# Proiect_TSC_v86.net
KiCad netlist of a schematic drawn in EAGLE
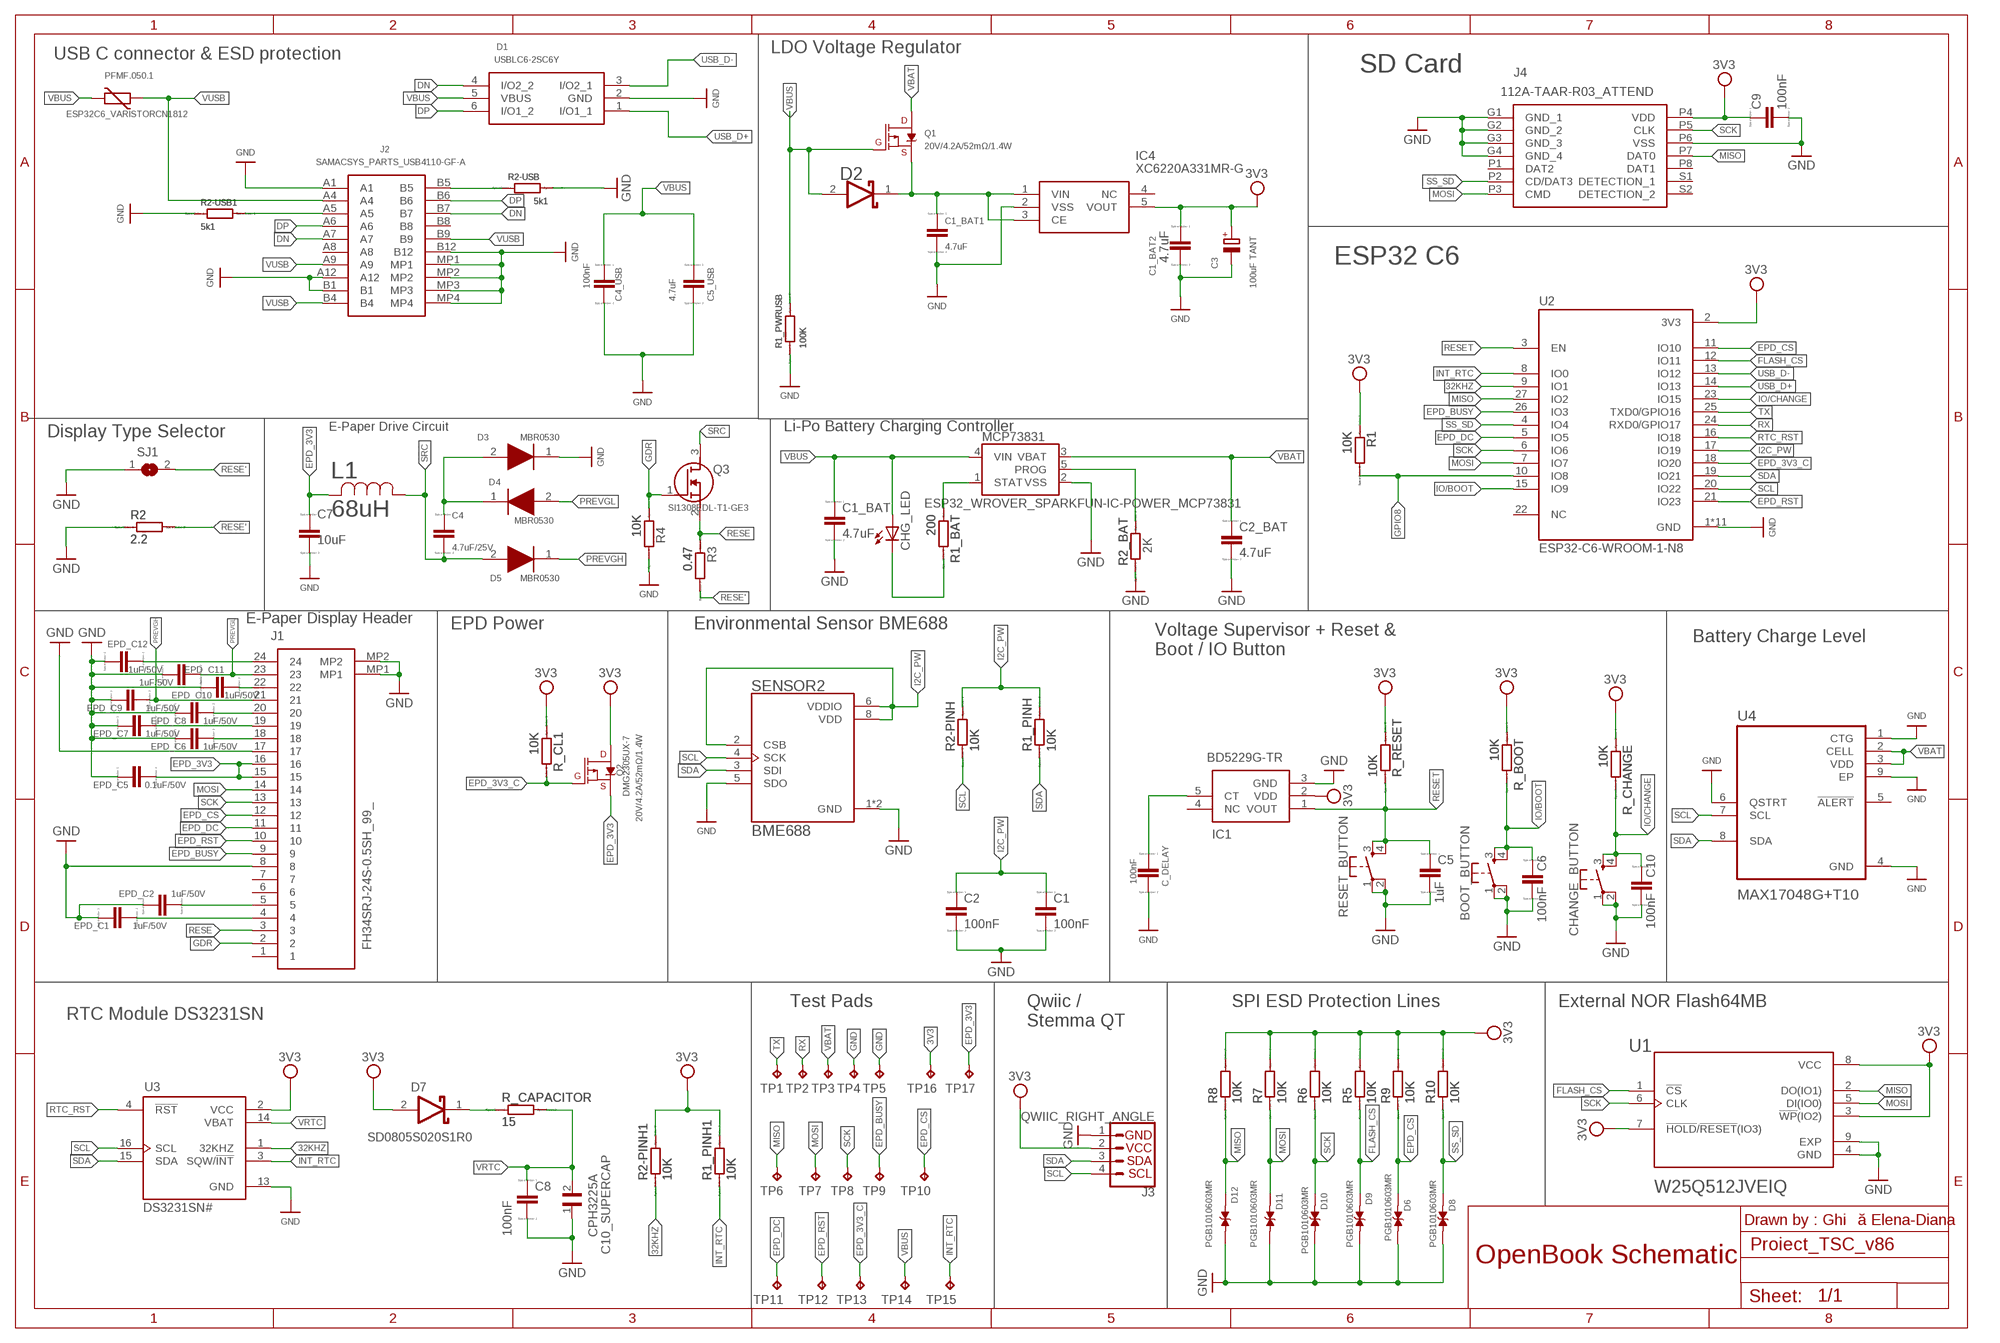
[diagram p0: schematic, sheet 1]

(export (version "E")
  (design (tool "Eeschema 10.0.6"))
  (components
    (comp (ref "BOOT_BUTTON")
      (value "BUTTON_CUSYOMV1")
      (footprint "eagle-import:MYBUTTON")
      (libsource (lib "eagle-import") (part "BUTTON_CUSYOMV1"))
    )
    (comp (ref "C1")
      (value "100nF")
      (footprint "eagle-import:ESP32_WROVER_EAGLE-LTSPICE_C0402")
      (libsource (lib "eagle-import") (part "ESP32_WROVER_EAGLE-LTSPICE_CC0402"))
    )
    (comp (ref "C1_BAT")
      (value "4.7uF")
      (footprint "eagle-import:ESP32_WROVER_EAGLE-LTSPICE_C0402")
      (libsource (lib "eagle-import") (part "ESP32_WROVER_EAGLE-LTSPICE_CC0402"))
    )
    (comp (ref "C1_BAT1")
      (value "4.7uF")
      (footprint "eagle-import:ESP32_WROVER_EAGLE-LTSPICE_C0402")
      (libsource (lib "eagle-import") (part "ESP32_WROVER_EAGLE-LTSPICE_CC0402"))
    )
    (comp (ref "C1_BAT2")
      (value "4.7uF")
      (footprint "eagle-import:ESP32_WROVER_EAGLE-LTSPICE_C0402")
      (libsource (lib "eagle-import") (part "ESP32_WROVER_EAGLE-LTSPICE_CC0402"))
    )
    (comp (ref "C2")
      (value "100nF")
      (footprint "eagle-import:ESP32_WROVER_EAGLE-LTSPICE_C0402")
      (libsource (lib "eagle-import") (part "ESP32_WROVER_EAGLE-LTSPICE_CC0402"))
    )
    (comp (ref "C2_BAT")
      (value "4.7uF")
      (footprint "eagle-import:ESP32_WROVER_EAGLE-LTSPICE_C0402")
      (libsource (lib "eagle-import") (part "ESP32_WROVER_EAGLE-LTSPICE_CC0402"))
    )
    (comp (ref "C3")
      (value "100uF TANT")
      (footprint "eagle-import:RCL_CT3528")
      (libsource (lib "eagle-import") (part "RCL_CPOL-EUCT3528"))
    )
    (comp (ref "C4")
      (value "4.7uF/25V")
      (footprint "eagle-import:ESP32_WROVER_EAGLE-LTSPICE_C0402")
      (libsource (lib "eagle-import") (part "ESP32_WROVER_EAGLE-LTSPICE_CC0402"))
    )
    (comp (ref "C4_USB")
      (value "100nF")
      (footprint "eagle-import:ESP32_WROVER_EAGLE-LTSPICE_C0402")
      (libsource (lib "eagle-import") (part "ESP32_WROVER_EAGLE-LTSPICE_CC0402"))
    )
    (comp (ref "C5")
      (value "1uF")
      (footprint "eagle-import:ESP32_WROVER_EAGLE-LTSPICE_C0402")
      (libsource (lib "eagle-import") (part "ESP32_WROVER_EAGLE-LTSPICE_CC0402"))
    )
    (comp (ref "C5_USB")
      (value "4.7uF")
      (footprint "eagle-import:ESP32_WROVER_EAGLE-LTSPICE_C0402")
      (libsource (lib "eagle-import") (part "ESP32_WROVER_EAGLE-LTSPICE_CC0402"))
    )
    (comp (ref "C6")
      (value "100nF")
      (footprint "eagle-import:ESP32_WROVER_EAGLE-LTSPICE_C0402")
      (libsource (lib "eagle-import") (part "ESP32_WROVER_EAGLE-LTSPICE_CC0402"))
    )
    (comp (ref "C7")
      (value "10uF")
      (footprint "eagle-import:ESP32_WROVER_EAGLE-LTSPICE_C0402")
      (libsource (lib "eagle-import") (part "ESP32_WROVER_EAGLE-LTSPICE_CC0402"))
    )
    (comp (ref "C8")
      (value "100nF")
      (footprint "eagle-import:ESP32_WROVER_EAGLE-LTSPICE_C0402")
      (libsource (lib "eagle-import") (part "ESP32_WROVER_EAGLE-LTSPICE_CC0402"))
    )
    (comp (ref "C9")
      (value "100nF")
      (footprint "eagle-import:ESP32_WROVER_EAGLE-LTSPICE_C0402")
      (libsource (lib "eagle-import") (part "ESP32_WROVER_EAGLE-LTSPICE_CC0402"))
    )
    (comp (ref "C10")
      (value "100nF")
      (footprint "eagle-import:ESP32_WROVER_EAGLE-LTSPICE_C0402")
      (libsource (lib "eagle-import") (part "ESP32_WROVER_EAGLE-LTSPICE_CC0402"))
    )
    (comp (ref "C10_SUPERCAP")
      (value "CPH3225A")
      (footprint "eagle-import:CAPCP3225X100N")
      (fields (field (name "MF") "Seiko Instruments"))
      (libsource (lib "eagle-import") (part "CPH3225A"))
    )
    (comp (ref "CHANGE_BUTTON")
      (value "BUTTON_CUSYOMV1")
      (footprint "eagle-import:MYBUTTON")
      (libsource (lib "eagle-import") (part "BUTTON_CUSYOMV1"))
    )
    (comp (ref "CHG_LED")
      (value "ADAFRUIT_LEDCHIP-LED0603")
      (footprint "eagle-import:ADAFRUIT_CHIP-LED0603")
      (libsource (lib "eagle-import") (part "ADAFRUIT_LEDCHIP-LED0603"))
    )
    (comp (ref "C_DELAY")
      (value "100nF")
      (footprint "eagle-import:ESP32_WROVER_EAGLE-LTSPICE_C0402")
      (libsource (lib "eagle-import") (part "ESP32_WROVER_EAGLE-LTSPICE_CC0402"))
    )
    (comp (ref "D1")
      (value "USBLC6-2SC6Y")
      (footprint "eagle-import:SOT95P280X145-6N")
      (fields (field (name "MF") "STMicroelectronics"))
      (libsource (lib "eagle-import") (part "USBLC6-2SC6Y"))
    )
    (comp (ref "D2")
      (value "ESP32_WROVER_AVX---SD0805S020S1R0_AVX_SD0805S020S1R0_0_0AVX_SD0805S020S1R0_0_0")
      (footprint "eagle-import:ESP32_WROVER_AVX---SD0805S020S1R0_AVX_SD0805S020S1R0_0")
      (fields
        (field (name "DIGIKEY_PART_NUMBER") "478-7800-1-ND")
        (field (name "MF") "AVX")
        (field (name "MOUSER_PART_NUMBER") "581-SD0805S020S1R0")
      )
      (libsource (lib "eagle-import") (part "ESP32_WROVER_AVX---SD0805S020S1R0_AVX_SD0805S020S1R0_0_0AVX_SD0805S020S1R0_0_0"))
    )
    (comp (ref "D3")
      (value "MBR0530")
      (footprint "eagle-import:SOD3716X135N")
      (fields (field (name "MF") "ON Semiconductor"))
      (libsource (lib "eagle-import") (part "MBR0530"))
    )
    (comp (ref "D4")
      (value "MBR0530")
      (footprint "eagle-import:SOD3716X135N")
      (fields (field (name "MF") "ON Semiconductor"))
      (libsource (lib "eagle-import") (part "MBR0530"))
    )
    (comp (ref "D5")
      (value "MBR0530")
      (footprint "eagle-import:SOD3716X135N")
      (fields (field (name "MF") "ON Semiconductor"))
      (libsource (lib "eagle-import") (part "MBR0530"))
    )
    (comp (ref "D6")
      (value "PGB1010603MR")
      (footprint "eagle-import:DIOC1608X36N")
      (fields (field (name "MF") "Littelfuse Inc."))
      (libsource (lib "eagle-import") (part "PGB1010603MR"))
    )
    (comp (ref "D7")
      (value "ESP32_WROVER_AVX---SD0805S020S1R0_AVX_SD0805S020S1R0_0_0AVX_SD0805S020S1R0_0_0")
      (footprint "eagle-import:ESP32_WROVER_AVX---SD0805S020S1R0_AVX_SD0805S020S1R0_0")
      (fields
        (field (name "DIGIKEY_PART_NUMBER") "478-7800-1-ND")
        (field (name "MF") "AVX")
        (field (name "MOUSER_PART_NUMBER") "581-SD0805S020S1R0")
      )
      (libsource (lib "eagle-import") (part "ESP32_WROVER_AVX---SD0805S020S1R0_AVX_SD0805S020S1R0_0_0AVX_SD0805S020S1R0_0_0"))
    )
    (comp (ref "D8")
      (value "PGB1010603MR")
      (footprint "eagle-import:DIOC1608X36N")
      (fields (field (name "MF") "Littelfuse Inc."))
      (libsource (lib "eagle-import") (part "PGB1010603MR"))
    )
    (comp (ref "D9")
      (value "PGB1010603MR")
      (footprint "eagle-import:DIOC1608X36N")
      (fields (field (name "MF") "Littelfuse Inc."))
      (libsource (lib "eagle-import") (part "PGB1010603MR"))
    )
    (comp (ref "D10")
      (value "PGB1010603MR")
      (footprint "eagle-import:DIOC1608X36N")
      (fields (field (name "MF") "Littelfuse Inc."))
      (libsource (lib "eagle-import") (part "PGB1010603MR"))
    )
    (comp (ref "D11")
      (value "PGB1010603MR")
      (footprint "eagle-import:DIOC1608X36N")
      (fields (field (name "MF") "Littelfuse Inc."))
      (libsource (lib "eagle-import") (part "PGB1010603MR"))
    )
    (comp (ref "D12")
      (value "PGB1010603MR")
      (footprint "eagle-import:DIOC1608X36N")
      (fields (field (name "MF") "Littelfuse Inc."))
      (libsource (lib "eagle-import") (part "PGB1010603MR"))
    )
    (comp (ref "EPD_C1")
      (value "1uF/50V")
      (footprint "eagle-import:ESP32_WROVER_EAGLE-LTSPICE_C0402")
      (libsource (lib "eagle-import") (part "ESP32_WROVER_EAGLE-LTSPICE_CC0402"))
    )
    (comp (ref "EPD_C2")
      (value "1uF/50V")
      (footprint "eagle-import:ESP32_WROVER_EAGLE-LTSPICE_C0402")
      (libsource (lib "eagle-import") (part "ESP32_WROVER_EAGLE-LTSPICE_CC0402"))
    )
    (comp (ref "EPD_C5")
      (value "0.1uF/50V")
      (footprint "eagle-import:ESP32_WROVER_EAGLE-LTSPICE_C0402")
      (libsource (lib "eagle-import") (part "ESP32_WROVER_EAGLE-LTSPICE_CC0402"))
    )
    (comp (ref "EPD_C6")
      (value "1uF/50V")
      (footprint "eagle-import:ESP32_WROVER_EAGLE-LTSPICE_C0402")
      (libsource (lib "eagle-import") (part "ESP32_WROVER_EAGLE-LTSPICE_CC0402"))
    )
    (comp (ref "EPD_C7")
      (value "1uF/50V")
      (footprint "eagle-import:ESP32_WROVER_EAGLE-LTSPICE_C0402")
      (libsource (lib "eagle-import") (part "ESP32_WROVER_EAGLE-LTSPICE_CC0402"))
    )
    (comp (ref "EPD_C8")
      (value "1uF/50V")
      (footprint "eagle-import:ESP32_WROVER_EAGLE-LTSPICE_C0402")
      (libsource (lib "eagle-import") (part "ESP32_WROVER_EAGLE-LTSPICE_CC0402"))
    )
    (comp (ref "EPD_C9")
      (value "1uF/50V")
      (footprint "eagle-import:ESP32_WROVER_EAGLE-LTSPICE_C0402")
      (libsource (lib "eagle-import") (part "ESP32_WROVER_EAGLE-LTSPICE_CC0402"))
    )
    (comp (ref "EPD_C10")
      (value "1uF/50V")
      (footprint "eagle-import:ESP32_WROVER_EAGLE-LTSPICE_C0402")
      (libsource (lib "eagle-import") (part "ESP32_WROVER_EAGLE-LTSPICE_CC0402"))
    )
    (comp (ref "EPD_C11")
      (value "1uF/50V")
      (footprint "eagle-import:ESP32_WROVER_EAGLE-LTSPICE_C0402")
      (libsource (lib "eagle-import") (part "ESP32_WROVER_EAGLE-LTSPICE_CC0402"))
    )
    (comp (ref "EPD_C12")
      (value "1uF/50V")
      (footprint "eagle-import:ESP32_WROVER_EAGLE-LTSPICE_C0402")
      (libsource (lib "eagle-import") (part "ESP32_WROVER_EAGLE-LTSPICE_CC0402"))
    )
    (comp (ref "IC1")
      (value "BD5229G-TR")
      (footprint "eagle-import:SOT95P280X125-5N")
      (fields (field (name "MOUSER_PART_NUMBER") "755-BD5229G-TR"))
      (libsource (lib "eagle-import") (part "BD5229G-TR"))
    )
    (comp (ref "IC4")
      (value "XC6220A331MR-G")
      (footprint "eagle-import:SOT95P280X120-5N")
      (fields (field (name "MOUSER_PART_NUMBER") "865-XC6220A331MR-G"))
      (libsource (lib "eagle-import") (part "XC6220A331MR-G"))
    )
    (comp (ref "J1")
      (value "FH34SRJ-24S-0.5SH_99_")
      (footprint "eagle-import:FH34SRJ24S05SH99")
      (fields
        (field (name "MANUFACTURER_PART_NUMBER") "FH34SRJ-24S-0.5SH(99)")
        (field (name "MOUSER_PART_NUMBER") "798-FH34SRJ24S05SH99")
      )
      (libsource (lib "eagle-import") (part "FH34SRJ-24S-0.5SH_99_"))
    )
    (comp (ref "J2")
      (value "SAMACSYS_PARTS_USB4110-GF-A")
      (footprint "eagle-import:SAMACSYS_PARTS_USB4110GFA")
      (fields
        (field (name "MANUFACTURER_PART_NUMBER") "USB4110-GF-A")
        (field (name "MOUSER_PART_NUMBER") "640-USB4110-GF-A")
      )
      (libsource (lib "eagle-import") (part "SAMACSYS_PARTS_USB4110-GF-A"))
    )
    (comp (ref "J3")
      (value "QWIIC_RIGHT_ANGLE")
      (footprint "eagle-import:JST04_1MM_RA")
      (libsource (lib "eagle-import") (part "QWIIC_CONNECTORJS-1MM"))
    )
    (comp (ref "J4")
      (value "112A-TAAR-R03_ATTEND")
      (footprint "eagle-import:112ATAARR03ATTEND")
      (fields (field (name "MANUFACTURER_PART_NUMBER") "112A-TAAR-R03 ATTEND"))
      (libsource (lib "eagle-import") (part "112A-TAAR-R03_ATTEND"))
    )
    (comp (ref "L1")
      (value "68uH")
      (footprint "eagle-import:IND_4828-WE-TPC_WRE")
      (fields
        (field (name "MANUFACTURER_PART_NUMBER") "744043680")
        (field (name "COPYRIGHT") "Copyright (C) 2024 Ultra Librarian. All rights reserved.")
      )
      (libsource (lib "eagle-import") (part "744043680IND_4828-WE-TPC_WRE"))
    )
    (comp (ref "MCP73831")
      (value "ESP32_WROVER_SPARKFUN-IC-POWER_MCP73831")
      (footprint "eagle-import:ESP32_WROVER_SPARKFUN-IC-POWER_SOT23-5")
      (libsource (lib "eagle-import") (part "ESP32_WROVER_SPARKFUN-IC-POWER_MCP73831"))
    )
    (comp (ref "PFMF.050.1")
      (value "ESP32C6_VARISTORCN1812")
      (footprint "eagle-import:ESP32C6_VARISTOR_CT_CN1812")
      (libsource (lib "eagle-import") (part "ESP32C6_VARISTORCN1812"))
    )
    (comp (ref "Q1")
      (value "20V/4.2A/52mΩ/1.4W")
      (footprint "eagle-import:ESP32_WROVER_SPARKFUN-DISCRETESEMI_SOT23-3")
      (libsource (lib "eagle-import") (part "ESP32_WROVER_SPARKFUN-DISCRETESEMI_MOSFET_PCH-DMG2305UX-7"))
    )
    (comp (ref "Q2")
      (value "20V/4.2A/52mΩ/1.4W")
      (footprint "eagle-import:ESP32_WROVER_SPARKFUN-DISCRETESEMI_SOT23-3")
      (fields (field (name "THERMALLOSS") "2305 UX"))
      (libsource (lib "eagle-import") (part "ESP32_WROVER_SPARKFUN-DISCRETESEMI_MOSFET_PCH-DMG2305UX-7"))
    )
    (comp (ref "Q3")
      (value "SI1308EDL-T1-GE3")
      (footprint "eagle-import:SOT65P210X110-3N")
      (fields (field (name "MF") "Vishay Siliconix"))
      (libsource (lib "eagle-import") (part "SI1308EDL-T1-GE3"))
    )
    (comp (ref "R1")
      (value "10K")
      (footprint "eagle-import:ESP32_WROVER_EAGLE-LTSPICE_R0402")
      (libsource (lib "eagle-import") (part "ESP32_WROVER_EAGLE-LTSPICE_RR0402"))
    )
    (comp (ref "R1_BAT")
      (value "200")
      (footprint "eagle-import:ESP32_WROVER_EAGLE-LTSPICE_R0402")
      (libsource (lib "eagle-import") (part "ESP32_WROVER_EAGLE-LTSPICE_RR0402"))
    )
    (comp (ref "R1_PINH")
      (value "10K")
      (footprint "eagle-import:ESP32_WROVER_EAGLE-LTSPICE_R0402")
      (libsource (lib "eagle-import") (part "ESP32_WROVER_EAGLE-LTSPICE_RR0402"))
    )
    (comp (ref "R1_PINH1")
      (value "10K")
      (footprint "eagle-import:ESP32_WROVER_EAGLE-LTSPICE_R0402")
      (libsource (lib "eagle-import") (part "ESP32_WROVER_EAGLE-LTSPICE_RR0402"))
    )
    (comp (ref "R1_PWRUSB")
      (value "100K")
      (footprint "eagle-import:ESP32_WROVER_EAGLE-LTSPICE_R0402")
      (libsource (lib "eagle-import") (part "ESP32_WROVER_EAGLE-LTSPICE_RR0402"))
    )
    (comp (ref "R2")
      (value "2.2")
      (footprint "eagle-import:ESP32_WROVER_EAGLE-LTSPICE_R0402")
      (libsource (lib "eagle-import") (part "ESP32_WROVER_EAGLE-LTSPICE_RR0402"))
    )
    (comp (ref "R2-PINH")
      (value "10K")
      (footprint "eagle-import:ESP32_WROVER_EAGLE-LTSPICE_R0402")
      (libsource (lib "eagle-import") (part "ESP32_WROVER_EAGLE-LTSPICE_RR0402"))
    )
    (comp (ref "R2-PINH1")
      (value "10K")
      (footprint "eagle-import:ESP32_WROVER_EAGLE-LTSPICE_R0402")
      (libsource (lib "eagle-import") (part "ESP32_WROVER_EAGLE-LTSPICE_RR0402"))
    )
    (comp (ref "R2-USB")
      (value "5k1")
      (footprint "eagle-import:ESP32_WROVER_EAGLE-LTSPICE_R0402")
      (libsource (lib "eagle-import") (part "ESP32_WROVER_EAGLE-LTSPICE_RR0402"))
    )
    (comp (ref "R2-USB1")
      (value "5k1")
      (footprint "eagle-import:ESP32_WROVER_EAGLE-LTSPICE_R0402")
      (libsource (lib "eagle-import") (part "ESP32_WROVER_EAGLE-LTSPICE_RR0402"))
    )
    (comp (ref "R2_BAT")
      (value "2K")
      (footprint "eagle-import:ESP32_WROVER_EAGLE-LTSPICE_R0402")
      (libsource (lib "eagle-import") (part "ESP32_WROVER_EAGLE-LTSPICE_RR0402"))
    )
    (comp (ref "R3")
      (value "0.47")
      (footprint "eagle-import:ESP32_WROVER_EAGLE-LTSPICE_R0402")
      (libsource (lib "eagle-import") (part "ESP32_WROVER_EAGLE-LTSPICE_RR0402"))
    )
    (comp (ref "R4")
      (value "10K")
      (footprint "eagle-import:ESP32_WROVER_EAGLE-LTSPICE_R0402")
      (libsource (lib "eagle-import") (part "ESP32_WROVER_EAGLE-LTSPICE_RR0402"))
    )
    (comp (ref "R5")
      (value "10K")
      (footprint "eagle-import:ESP32_WROVER_EAGLE-LTSPICE_R0402")
      (libsource (lib "eagle-import") (part "ESP32_WROVER_EAGLE-LTSPICE_RR0402"))
    )
    (comp (ref "R6")
      (value "10K")
      (footprint "eagle-import:ESP32_WROVER_EAGLE-LTSPICE_R0402")
      (libsource (lib "eagle-import") (part "ESP32_WROVER_EAGLE-LTSPICE_RR0402"))
    )
    (comp (ref "R7")
      (value "10K")
      (footprint "eagle-import:ESP32_WROVER_EAGLE-LTSPICE_R0402")
      (libsource (lib "eagle-import") (part "ESP32_WROVER_EAGLE-LTSPICE_RR0402"))
    )
    (comp (ref "R8")
      (value "10K")
      (footprint "eagle-import:ESP32_WROVER_EAGLE-LTSPICE_R0402")
      (libsource (lib "eagle-import") (part "ESP32_WROVER_EAGLE-LTSPICE_RR0402"))
    )
    (comp (ref "R9")
      (value "10K")
      (footprint "eagle-import:ESP32_WROVER_EAGLE-LTSPICE_R0402")
      (libsource (lib "eagle-import") (part "ESP32_WROVER_EAGLE-LTSPICE_RR0402"))
    )
    (comp (ref "R10")
      (value "10K")
      (footprint "eagle-import:ESP32_WROVER_EAGLE-LTSPICE_R0402")
      (libsource (lib "eagle-import") (part "ESP32_WROVER_EAGLE-LTSPICE_RR0402"))
    )
    (comp (ref "RESET_BUTTON")
      (value "BUTTON_CUSYOMV1")
      (footprint "eagle-import:MYBUTTON")
      (libsource (lib "eagle-import") (part "BUTTON_CUSYOMV1"))
    )
    (comp (ref "R_BOOT")
      (value "10K")
      (footprint "eagle-import:ESP32_WROVER_EAGLE-LTSPICE_R0402")
      (libsource (lib "eagle-import") (part "ESP32_WROVER_EAGLE-LTSPICE_RR0402"))
    )
    (comp (ref "R_CAPACITOR")
      (value "15")
      (footprint "eagle-import:ESP32_WROVER_EAGLE-LTSPICE_R0402")
      (libsource (lib "eagle-import") (part "ESP32_WROVER_EAGLE-LTSPICE_RR0402"))
    )
    (comp (ref "R_CHANGE")
      (value "10K")
      (footprint "eagle-import:ESP32_WROVER_EAGLE-LTSPICE_R0402")
      (libsource (lib "eagle-import") (part "ESP32_WROVER_EAGLE-LTSPICE_RR0402"))
    )
    (comp (ref "R_CL1")
      (value "10K")
      (footprint "eagle-import:ESP32_WROVER_EAGLE-LTSPICE_R0402")
      (libsource (lib "eagle-import") (part "ESP32_WROVER_EAGLE-LTSPICE_RR0402"))
    )
    (comp (ref "R_RESET")
      (value "10K")
      (footprint "eagle-import:ESP32_WROVER_EAGLE-LTSPICE_R0402")
      (libsource (lib "eagle-import") (part "ESP32_WROVER_EAGLE-LTSPICE_RR0402"))
    )
    (comp (ref "SENSOR2")
      (value "BME688")
      (footprint "eagle-import:ESP32_WROVER_BME680_PSON80P300X300X100-8N")
      (fields (field (name "MF") "Bosch Sensortec") (field (name "MP") "BME680"))
      (libsource (lib "eagle-import") (part "ESP32_WROVER_BME680_BME680"))
    )
    (comp (ref "SJ1") (value "SJ") (footprint "eagle-import:SJ") (libsource (lib "eagle-import") (part "SJ")))
    (comp (ref "TP1")
      (value "TPTP20R")
      (footprint "eagle-import:TP20R")
      (libsource (lib "eagle-import") (part "TPTP20R"))
    )
    (comp (ref "TP2")
      (value "TPTP20R")
      (footprint "eagle-import:TP20R")
      (libsource (lib "eagle-import") (part "TPTP20R"))
    )
    (comp (ref "TP3")
      (value "TPTP20R")
      (footprint "eagle-import:TP20R")
      (libsource (lib "eagle-import") (part "TPTP20R"))
    )
    (comp (ref "TP4")
      (value "TPTP20R")
      (footprint "eagle-import:TP20R")
      (libsource (lib "eagle-import") (part "TPTP20R"))
    )
    (comp (ref "TP5")
      (value "TPTP20R")
      (footprint "eagle-import:TP20R")
      (libsource (lib "eagle-import") (part "TPTP20R"))
    )
    (comp (ref "TP6")
      (value "TPTP20R")
      (footprint "eagle-import:TP20R")
      (libsource (lib "eagle-import") (part "TPTP20R"))
    )
    (comp (ref "TP7")
      (value "TPTP20R")
      (footprint "eagle-import:TP20R")
      (libsource (lib "eagle-import") (part "TPTP20R"))
    )
    (comp (ref "TP8")
      (value "TPTP20R")
      (footprint "eagle-import:TP20R")
      (libsource (lib "eagle-import") (part "TPTP20R"))
    )
    (comp (ref "TP9")
      (value "TPTP20R")
      (footprint "eagle-import:TP20R")
      (libsource (lib "eagle-import") (part "TPTP20R"))
    )
    (comp (ref "TP10")
      (value "TPTP20R")
      (footprint "eagle-import:TP20R")
      (libsource (lib "eagle-import") (part "TPTP20R"))
    )
    (comp (ref "TP11")
      (value "TPTP20R")
      (footprint "eagle-import:TP20R")
      (libsource (lib "eagle-import") (part "TPTP20R"))
    )
    (comp (ref "TP12")
      (value "TPTP20R")
      (footprint "eagle-import:TP20R")
      (libsource (lib "eagle-import") (part "TPTP20R"))
    )
    (comp (ref "TP13")
      (value "TPTP20R")
      (footprint "eagle-import:TP20R")
      (libsource (lib "eagle-import") (part "TPTP20R"))
    )
    (comp (ref "TP14")
      (value "TPTP20R")
      (footprint "eagle-import:TP20R")
      (libsource (lib "eagle-import") (part "TPTP20R"))
    )
    (comp (ref "TP15")
      (value "TPTP20R")
      (footprint "eagle-import:TP20R")
      (libsource (lib "eagle-import") (part "TPTP20R"))
    )
    (comp (ref "TP16")
      (value "TPTP20R")
      (footprint "eagle-import:TP20R")
      (libsource (lib "eagle-import") (part "TPTP20R"))
    )
    (comp (ref "TP17")
      (value "TPTP20R")
      (footprint "eagle-import:TP20R")
      (libsource (lib "eagle-import") (part "TPTP20R"))
    )
    (comp (ref "U1")
      (value "W25Q512JVEIQ")
      (footprint "eagle-import:SON127P600X800X80-9N")
      (fields (field (name "MF") "Winbond Electronics"))
      (libsource (lib "eagle-import") (part "W25Q512JVEIQ"))
    )
    (comp (ref "U2")
      (value "ESP32-C6-WROOM-1-N8")
      (footprint "eagle-import:XCVR_ESP32-C6-WROOM-1-N8")
      (fields (field (name "MF") "Espressif Systems"))
      (libsource (lib "eagle-import") (part "ESP32-C6-WROOM-1-N8"))
    )
    (comp (ref "U3")
      (value "DS3231SN#")
      (footprint "eagle-import:SOIC127P1032X265-16N")
      (fields (field (name "MF") "Analog Devices"))
      (libsource (lib "eagle-import") (part "DS3231SN#"))
    )
    (comp (ref "U4")
      (value "MAX17048G+T10")
      (footprint "eagle-import:SON50P200X200X80-9N")
      (fields (field (name "MF") "Analog Devices"))
      (libsource (lib "eagle-import") (part "MAX17048G+T10"))
    )
  )
  (nets
    (net (code "1") (name "3V3") (class "Default")
      (node (ref "C1_BAT2") (pin "1") (pinfunction "1_1") (pintype "passive"))
      (node (ref "C3") (pin "+") (pinfunction "+_+") (pintype "passive"))
      (node (ref "C9") (pin "1") (pinfunction "1_1") (pintype "passive"))
      (node (ref "D7") (pin "2") (pinfunction "ANODE_2") (pintype "bidirectional"))
      (node (ref "IC1") (pin "2") (pinfunction "VDD_2") (pintype "bidirectional"))
      (node (ref "IC4") (pin "5") (pinfunction "VOUT_5") (pintype "bidirectional"))
      (node (ref "J3") (pin "2") (pinfunction "2_2") (pintype "power_in"))
      (node (ref "J4") (pin "P4") (pinfunction "VDD_P4") (pintype "bidirectional"))
      (node (ref "Q2") (pin "3") (pinfunction "D_3") (pintype "bidirectional"))
      (node (ref "R1") (pin "1") (pinfunction "1_1") (pintype "passive"))
      (node (ref "R10") (pin "2") (pinfunction "2_2") (pintype "passive"))
      (node (ref "R1_PINH1") (pin "2") (pinfunction "2_2") (pintype "passive"))
      (node (ref "R2-PINH1") (pin "2") (pinfunction "2_2") (pintype "passive"))
      (node (ref "R5") (pin "2") (pinfunction "2_2") (pintype "passive"))
      (node (ref "R6") (pin "2") (pinfunction "2_2") (pintype "passive"))
      (node (ref "R7") (pin "2") (pinfunction "2_2") (pintype "passive"))
      (node (ref "R8") (pin "2") (pinfunction "2_2") (pintype "passive"))
      (node (ref "R9") (pin "2") (pinfunction "2_2") (pintype "passive"))
      (node (ref "R_BOOT") (pin "1") (pinfunction "1_1") (pintype "passive"))
      (node (ref "R_CHANGE") (pin "1") (pinfunction "1_1") (pintype "passive"))
      (node (ref "R_CL1") (pin "1") (pinfunction "1_1") (pintype "passive"))
      (node (ref "R_RESET") (pin "2") (pinfunction "2_2") (pintype "passive"))
      (node (ref "TP16") (pin "TP") (pinfunction "TP_TP") (pintype "input"))
      (node (ref "U1") (pin "3") (pinfunction "~{WP}(IO2)_3") (pintype "bidirectional"))
      (node (ref "U1") (pin "7") (pinfunction "~{HOLD}/~{RESET}(IO3)_7") (pintype "bidirectional"))
      (node (ref "U1") (pin "8") (pinfunction "VCC_8") (pintype "power_in"))
      (node (ref "U2") (pin "2") (pinfunction "3V3_2") (pintype "power_in"))
      (node (ref "U3") (pin "2") (pinfunction "VCC_2") (pintype "power_in"))
    )
    (net (code "2") (name "32KHZ") (class "Default")
      (node (ref "R2-PINH1") (pin "1") (pinfunction "1_1") (pintype "passive"))
      (node (ref "U2") (pin "9") (pinfunction "IO1_9") (pintype "bidirectional"))
      (node (ref "U3") (pin "1") (pinfunction "32KHZ_1") (pintype "output"))
    )
    (net (code "3") (name "DN") (class "Default")
      (node (ref "D1") (pin "4") (pinfunction "I/O2_2_4") (pintype "bidirectional"))
      (node (ref "J2") (pin "A7") (pinfunction "A7_A7") (pintype "bidirectional"))
      (node (ref "J2") (pin "B7") (pinfunction "B7_B7") (pintype "bidirectional"))
    )
    (net (code "4") (name "DP") (class "Default")
      (node (ref "D1") (pin "6") (pinfunction "I/O1_2_6") (pintype "bidirectional"))
      (node (ref "J2") (pin "A6") (pinfunction "A6_A6") (pintype "bidirectional"))
      (node (ref "J2") (pin "B6") (pinfunction "B6_B6") (pintype "bidirectional"))
    )
    (net (code "5") (name "EPD_3V3") (class "Default")
      (node (ref "C7") (pin "1") (pinfunction "1_1") (pintype "passive"))
      (node (ref "EPD_C5") (pin "2") (pinfunction "2_2") (pintype "passive"))
      (node (ref "J1") (pin "15") (pinfunction "15_15") (pintype "bidirectional"))
      (node (ref "J1") (pin "16") (pinfunction "16_16") (pintype "bidirectional"))
      (node (ref "L1") (pin "2") (pinfunction "2_2") (pintype "passive"))
      (node (ref "Q2") (pin "2") (pinfunction "S_2") (pintype "bidirectional"))
      (node (ref "TP17") (pin "TP") (pinfunction "TP_TP") (pintype "input"))
    )
    (net (code "6") (name "EPD_3V3_C") (class "Default")
      (node (ref "Q2") (pin "1") (pinfunction "G_1") (pintype "bidirectional"))
      (node (ref "R_CL1") (pin "2") (pinfunction "2_2") (pintype "passive"))
      (node (ref "TP13") (pin "TP") (pinfunction "TP_TP") (pintype "input"))
      (node (ref "U2") (pin "18") (pinfunction "IO20_18") (pintype "bidirectional"))
    )
    (net (code "7") (name "EPD_BUSY") (class "Default")
      (node (ref "J1") (pin "9") (pinfunction "9_9") (pintype "bidirectional"))
      (node (ref "TP9") (pin "TP") (pinfunction "TP_TP") (pintype "input"))
      (node (ref "U2") (pin "26") (pinfunction "IO3_26") (pintype "bidirectional"))
    )
    (net (code "8") (name "EPD_CS") (class "Default")
      (node (ref "D6") (pin "1") (pinfunction "1_1") (pintype "passive"))
      (node (ref "J1") (pin "12") (pinfunction "12_12") (pintype "bidirectional"))
      (node (ref "R9") (pin "1") (pinfunction "1_1") (pintype "passive"))
      (node (ref "TP10") (pin "TP") (pinfunction "TP_TP") (pintype "input"))
      (node (ref "U2") (pin "11") (pinfunction "IO10_11") (pintype "bidirectional"))
    )
    (net (code "9") (name "EPD_DC") (class "Default")
      (node (ref "J1") (pin "11") (pinfunction "11_11") (pintype "bidirectional"))
      (node (ref "TP11") (pin "TP") (pinfunction "TP_TP") (pintype "input"))
      (node (ref "U2") (pin "5") (pinfunction "IO5_5") (pintype "bidirectional"))
    )
    (net (code "10") (name "EPD_RST") (class "Default")
      (node (ref "J1") (pin "10") (pinfunction "10_10") (pintype "bidirectional"))
      (node (ref "TP12") (pin "TP") (pinfunction "TP_TP") (pintype "input"))
      (node (ref "U2") (pin "21") (pinfunction "IO23_21") (pintype "bidirectional"))
    )
    (net (code "11") (name "FLASH_CS") (class "Default")
      (node (ref "D9") (pin "1") (pinfunction "1_1") (pintype "passive"))
      (node (ref "R5") (pin "1") (pinfunction "1_1") (pintype "passive"))
      (node (ref "U1") (pin "1") (pinfunction "~{CS}_1") (pintype "input"))
      (node (ref "U2") (pin "12") (pinfunction "IO11_12") (pintype "bidirectional"))
    )
    (net (code "12") (name "GDR") (class "Default")
      (node (ref "J1") (pin "2") (pinfunction "2_2") (pintype "bidirectional"))
      (node (ref "Q3") (pin "1") (pinfunction "G_1") (pintype "bidirectional"))
      (node (ref "R4") (pin "1") (pinfunction "1_1") (pintype "passive"))
    )
    (net (code "13") (name "GND") (class "Default")
      (node (ref "BOOT_BUTTON") (pin "1") (pinfunction "1_1") (pintype "passive"))
      (node (ref "BOOT_BUTTON") (pin "2") (pinfunction "2_2") (pintype "passive"))
      (node (ref "C1") (pin "2") (pinfunction "2_2") (pintype "passive"))
      (node (ref "C10") (pin "2") (pinfunction "2_2") (pintype "passive"))
      (node (ref "C10_SUPERCAP") (pin "1") (pinfunction "1_1") (pintype "passive"))
      (node (ref "C1_BAT") (pin "2") (pinfunction "2_2") (pintype "passive"))
      (node (ref "C1_BAT1") (pin "2") (pinfunction "2_2") (pintype "passive"))
      (node (ref "C1_BAT2") (pin "2") (pinfunction "2_2") (pintype "passive"))
      (node (ref "C2") (pin "2") (pinfunction "2_2") (pintype "passive"))
      (node (ref "C2_BAT") (pin "2") (pinfunction "2_2") (pintype "passive"))
      (node (ref "C3") (pin "-") (pinfunction "-_-") (pintype "passive"))
      (node (ref "C4_USB") (pin "2") (pinfunction "2_2") (pintype "passive"))
      (node (ref "C5") (pin "2") (pinfunction "2_2") (pintype "passive"))
      (node (ref "C5_USB") (pin "2") (pinfunction "2_2") (pintype "passive"))
      (node (ref "C6") (pin "2") (pinfunction "2_2") (pintype "passive"))
      (node (ref "C7") (pin "2") (pinfunction "2_2") (pintype "passive"))
      (node (ref "C8") (pin "2") (pinfunction "2_2") (pintype "passive"))
      (node (ref "C9") (pin "2") (pinfunction "2_2") (pintype "passive"))
      (node (ref "CHANGE_BUTTON") (pin "1") (pinfunction "1_1") (pintype "passive"))
      (node (ref "CHANGE_BUTTON") (pin "2") (pinfunction "2_2") (pintype "passive"))
      (node (ref "C_DELAY") (pin "2") (pinfunction "2_2") (pintype "passive"))
      (node (ref "D1") (pin "2") (pinfunction "GND_2") (pintype "bidirectional"))
      (node (ref "D10") (pin "2") (pinfunction "2_2") (pintype "passive"))
      (node (ref "D11") (pin "2") (pinfunction "2_2") (pintype "passive"))
      (node (ref "D12") (pin "2") (pinfunction "2_2") (pintype "passive"))
      (node (ref "D3") (pin "1") (pinfunction "K_1") (pintype "bidirectional"))
      (node (ref "D6") (pin "2") (pinfunction "2_2") (pintype "passive"))
      (node (ref "D8") (pin "2") (pinfunction "2_2") (pintype "passive"))
      (node (ref "D9") (pin "2") (pinfunction "2_2") (pintype "passive"))
      (node (ref "EPD_C1") (pin "1") (pinfunction "1_1") (pintype "passive"))
      (node (ref "EPD_C10") (pin "1") (pinfunction "1_1") (pintype "passive"))
      (node (ref "EPD_C11") (pin "1") (pinfunction "1_1") (pintype "passive"))
      (node (ref "EPD_C12") (pin "1") (pinfunction "1_1") (pintype "passive"))
      (node (ref "EPD_C2") (pin "1") (pinfunction "1_1") (pintype "passive"))
      (node (ref "EPD_C5") (pin "1") (pinfunction "1_1") (pintype "passive"))
      (node (ref "EPD_C6") (pin "1") (pinfunction "1_1") (pintype "passive"))
      (node (ref "EPD_C7") (pin "1") (pinfunction "1_1") (pintype "passive"))
      (node (ref "EPD_C8") (pin "1") (pinfunction "1_1") (pintype "passive"))
      (node (ref "EPD_C9") (pin "1") (pinfunction "1_1") (pintype "passive"))
      (node (ref "IC1") (pin "3") (pinfunction "GND_3") (pintype "bidirectional"))
      (node (ref "IC4") (pin "2") (pinfunction "VSS_2") (pintype "bidirectional"))
      (node (ref "J1") (pin "17") (pinfunction "17_17") (pintype "bidirectional"))
      (node (ref "J1") (pin "8") (pinfunction "8_8") (pintype "bidirectional"))
      (node (ref "J1") (pin "MP1") (pinfunction "MP1_MP1") (pintype "bidirectional"))
      (node (ref "J1") (pin "MP2") (pinfunction "MP2_MP2") (pintype "bidirectional"))
      (node (ref "J2") (pin "A1") (pinfunction "A1_A1") (pintype "bidirectional"))
      (node (ref "J2") (pin "A12") (pinfunction "A12_A12") (pintype "bidirectional"))
      (node (ref "J2") (pin "B1") (pinfunction "B1_B1") (pintype "bidirectional"))
      (node (ref "J2") (pin "B12") (pinfunction "B12_B12") (pintype "bidirectional"))
      (node (ref "J2") (pin "MP1") (pinfunction "MP1_MP1") (pintype "bidirectional"))
      (node (ref "J2") (pin "MP2") (pinfunction "MP2_MP2") (pintype "bidirectional"))
      (node (ref "J2") (pin "MP3") (pinfunction "MP3_MP3") (pintype "bidirectional"))
      (node (ref "J2") (pin "MP4") (pinfunction "MP4_MP4") (pintype "bidirectional"))
      (node (ref "J3") (pin "1") (pinfunction "1_1") (pintype "power_in"))
      (node (ref "J4") (pin "G1") (pinfunction "GND_1_G1") (pintype "bidirectional"))
      (node (ref "J4") (pin "G2") (pinfunction "GND_2_G2") (pintype "bidirectional"))
      (node (ref "J4") (pin "G3") (pinfunction "GND_3_G3") (pintype "bidirectional"))
      (node (ref "J4") (pin "G4") (pinfunction "GND_4_G4") (pintype "bidirectional"))
      (node (ref "J4") (pin "P6") (pinfunction "VSS_P6") (pintype "bidirectional"))
      (node (ref "MCP73831") (pin "2") (pinfunction "VSS_2") (pintype "power_in"))
      (node (ref "R1_PWRUSB") (pin "1") (pinfunction "1_1") (pintype "passive"))
      (node (ref "R2") (pin "1") (pinfunction "1_1") (pintype "passive"))
      (node (ref "R2-USB") (pin "2") (pinfunction "2_2") (pintype "passive"))
      (node (ref "R2-USB1") (pin "1") (pinfunction "1_1") (pintype "passive"))
      (node (ref "R2_BAT") (pin "1") (pinfunction "1_1") (pintype "passive"))
      (node (ref "R4") (pin "2") (pinfunction "2_2") (pintype "passive"))
      (node (ref "RESET_BUTTON") (pin "1") (pinfunction "1_1") (pintype "passive"))
      (node (ref "RESET_BUTTON") (pin "2") (pinfunction "2_2") (pintype "passive"))
      (node (ref "SENSOR2") (pin "1") (pinfunction "GND_1") (pintype "power_in"))
      (node (ref "SENSOR2") (pin "5") (pinfunction "SDO_5") (pintype "bidirectional"))
      (node (ref "SENSOR2") (pin "7") (pinfunction "GND_7") (pintype "power_in"))
      (node (ref "SJ1") (pin "1") (pinfunction "1_1") (pintype "passive"))
      (node (ref "TP4") (pin "TP") (pinfunction "TP_TP") (pintype "input"))
      (node (ref "TP5") (pin "TP") (pinfunction "TP_TP") (pintype "input"))
      (node (ref "U1") (pin "4") (pinfunction "GND_4") (pintype "power_in"))
      (node (ref "U1") (pin "9") (pinfunction "EXP_9") (pintype "passive"))
      (node (ref "U2") (pin "1") (pinfunction "GND_1") (pintype "power_in"))
      (node (ref "U2") (pin "28") (pinfunction "GND_28") (pintype "power_in"))
      (node (ref "U2") (pin "29_1") (pinfunction "GND_29_1") (pintype "power_in"))
      (node (ref "U2") (pin "29_2") (pinfunction "GND_29_2") (pintype "power_in"))
      (node (ref "U2") (pin "29_3") (pinfunction "GND_29_3") (pintype "power_in"))
      (node (ref "U2") (pin "29_4") (pinfunction "GND_29_4") (pintype "power_in"))
      (node (ref "U2") (pin "29_5") (pinfunction "GND_29_5") (pintype "power_in"))
      (node (ref "U2") (pin "29_6") (pinfunction "GND_29_6") (pintype "power_in"))
      (node (ref "U2") (pin "29_7") (pinfunction "GND_29_7") (pintype "power_in"))
      (node (ref "U2") (pin "29_8") (pinfunction "GND_29_8") (pintype "power_in"))
      (node (ref "U2") (pin "29_9") (pinfunction "GND_29_9") (pintype "power_in"))
      (node (ref "U3") (pin "13") (pinfunction "GND_13") (pintype "power_in"))
      (node (ref "U4") (pin "1") (pinfunction "CTG_1") (pintype "power_in"))
      (node (ref "U4") (pin "4") (pinfunction "GND_4") (pintype "power_in"))
      (node (ref "U4") (pin "6") (pinfunction "QSTRT_6") (pintype "input"))
      (node (ref "U4") (pin "9") (pinfunction "EP_9") (pintype "power_in"))
    )
    (net (code "14") (name "GPIO8") (class "Default")
      (node (ref "R1") (pin "2") (pinfunction "2_2") (pintype "passive"))
      (node (ref "U2") (pin "10") (pinfunction "IO8_10") (pintype "bidirectional"))
    )
    (net (code "15") (name "I2C_PW") (class "Default")
      (node (ref "C1") (pin "1") (pinfunction "1_1") (pintype "passive"))
      (node (ref "C2") (pin "1") (pinfunction "1_1") (pintype "passive"))
      (node (ref "R1_PINH") (pin "2") (pinfunction "2_2") (pintype "passive"))
      (node (ref "R2-PINH") (pin "2") (pinfunction "2_2") (pintype "passive"))
      (node (ref "SENSOR2") (pin "2") (pinfunction "CSB_2") (pintype "input"))
      (node (ref "SENSOR2") (pin "6") (pinfunction "VDDIO_6") (pintype "power_in"))
      (node (ref "SENSOR2") (pin "8") (pinfunction "VDD_8") (pintype "power_in"))
      (node (ref "U2") (pin "17") (pinfunction "IO19_17") (pintype "bidirectional"))
    )
    (net (code "16") (name "INT_RTC") (class "Default")
      (node (ref "R1_PINH1") (pin "1") (pinfunction "1_1") (pintype "passive"))
      (node (ref "TP15") (pin "TP") (pinfunction "TP_TP") (pintype "input"))
      (node (ref "U2") (pin "8") (pinfunction "IO0_8") (pintype "bidirectional"))
      (node (ref "U3") (pin "3") (pinfunction "SQW/~{INT}_3") (pintype "output"))
    )
    (net (code "17") (name "IO{slash}BOOT") (class "Default")
      (node (ref "BOOT_BUTTON") (pin "3") (pinfunction "3_3") (pintype "passive"))
      (node (ref "BOOT_BUTTON") (pin "4") (pinfunction "4_4") (pintype "passive"))
      (node (ref "C6") (pin "1") (pinfunction "1_1") (pintype "passive"))
      (node (ref "R_BOOT") (pin "2") (pinfunction "2_2") (pintype "passive"))
      (node (ref "U2") (pin "15") (pinfunction "IO9_15") (pintype "bidirectional"))
    )
    (net (code "18") (name "IO{slash}CHANGE") (class "Default")
      (node (ref "C10") (pin "1") (pinfunction "1_1") (pintype "passive"))
      (node (ref "CHANGE_BUTTON") (pin "3") (pinfunction "3_3") (pintype "passive"))
      (node (ref "CHANGE_BUTTON") (pin "4") (pinfunction "4_4") (pintype "passive"))
      (node (ref "R_CHANGE") (pin "2") (pinfunction "2_2") (pintype "passive"))
      (node (ref "U2") (pin "23") (pinfunction "IO15_23") (pintype "bidirectional"))
    )
    (net (code "19") (name "MISO") (class "Default")
      (node (ref "D12") (pin "1") (pinfunction "1_1") (pintype "passive"))
      (node (ref "J4") (pin "P7") (pinfunction "DAT0_P7") (pintype "bidirectional"))
      (node (ref "R8") (pin "1") (pinfunction "1_1") (pintype "passive"))
      (node (ref "TP6") (pin "TP") (pinfunction "TP_TP") (pintype "input"))
      (node (ref "U1") (pin "2") (pinfunction "DO(IO1)_2") (pintype "bidirectional"))
      (node (ref "U2") (pin "27") (pinfunction "IO2_27") (pintype "bidirectional"))
    )
    (net (code "20") (name "MOSI") (class "Default")
      (node (ref "D11") (pin "1") (pinfunction "1_1") (pintype "passive"))
      (node (ref "J1") (pin "14") (pinfunction "14_14") (pintype "bidirectional"))
      (node (ref "J4") (pin "P3") (pinfunction "CMD_P3") (pintype "bidirectional"))
      (node (ref "R7") (pin "1") (pinfunction "1_1") (pintype "passive"))
      (node (ref "TP7") (pin "TP") (pinfunction "TP_TP") (pintype "input"))
      (node (ref "U1") (pin "5") (pinfunction "DI(IO0)_5") (pintype "bidirectional"))
      (node (ref "U2") (pin "7") (pinfunction "IO7_7") (pintype "bidirectional"))
    )
    (net (code "21") (name "Net-(CHG_LED-PadC)") (class "Default")
      (node (ref "CHG_LED") (pin "C") (pinfunction "C_C") (pintype "passive"))
      (node (ref "R1_BAT") (pin "2") (pinfunction "2_2") (pintype "passive"))
    )
    (net (code "22") (name "Net-(D2-CATHODE)") (class "Default")
      (node (ref "C1_BAT1") (pin "1") (pinfunction "1_1") (pintype "passive"))
      (node (ref "D2") (pin "1") (pinfunction "CATHODE_1") (pintype "bidirectional"))
      (node (ref "IC4") (pin "1") (pinfunction "VIN_1") (pintype "bidirectional"))
      (node (ref "IC4") (pin "3") (pinfunction "CE_3") (pintype "bidirectional"))
      (node (ref "Q1") (pin "2") (pinfunction "S_2") (pintype "bidirectional"))
    )
    (net (code "23") (name "Net-(D3-A)") (class "Default")
      (node (ref "C4") (pin "1") (pinfunction "1_1") (pintype "passive"))
      (node (ref "D3") (pin "2") (pinfunction "A_2") (pintype "bidirectional"))
      (node (ref "D4") (pin "1") (pinfunction "K_1") (pintype "bidirectional"))
    )
    (net (code "24") (name "Net-(D7-CATHODE)") (class "Default")
      (node (ref "D7") (pin "1") (pinfunction "CATHODE_1") (pintype "bidirectional"))
      (node (ref "R_CAPACITOR") (pin "1") (pinfunction "1_1") (pintype "passive"))
    )
    (net (code "25") (name "Net-(EPD_C1-Pad2)") (class "Default")
      (node (ref "EPD_C1") (pin "2") (pinfunction "2_2") (pintype "passive"))
      (node (ref "J1") (pin "4") (pinfunction "4_4") (pintype "bidirectional"))
    )
    (net (code "26") (name "Net-(EPD_C2-Pad2)") (class "Default")
      (node (ref "EPD_C2") (pin "2") (pinfunction "2_2") (pintype "passive"))
      (node (ref "J1") (pin "5") (pinfunction "5_5") (pintype "bidirectional"))
    )
    (net (code "27") (name "Net-(EPD_C6-Pad2)") (class "Default")
      (node (ref "EPD_C6") (pin "2") (pinfunction "2_2") (pintype "passive"))
      (node (ref "J1") (pin "18") (pinfunction "18_18") (pintype "bidirectional"))
    )
    (net (code "28") (name "Net-(EPD_C7-Pad2)") (class "Default")
      (node (ref "EPD_C7") (pin "2") (pinfunction "2_2") (pintype "passive"))
      (node (ref "J1") (pin "19") (pinfunction "19_19") (pintype "bidirectional"))
    )
    (net (code "29") (name "Net-(EPD_C8-Pad2)") (class "Default")
      (node (ref "EPD_C8") (pin "2") (pinfunction "2_2") (pintype "passive"))
      (node (ref "J1") (pin "20") (pinfunction "20_20") (pintype "bidirectional"))
    )
    (net (code "30") (name "Net-(EPD_C10-Pad2)") (class "Default")
      (node (ref "EPD_C10") (pin "2") (pinfunction "2_2") (pintype "passive"))
      (node (ref "J1") (pin "22") (pinfunction "22_22") (pintype "bidirectional"))
    )
    (net (code "31") (name "Net-(EPD_C12-Pad2)") (class "Default")
      (node (ref "EPD_C12") (pin "2") (pinfunction "2_2") (pintype "passive"))
      (node (ref "J1") (pin "24") (pinfunction "24_24") (pintype "bidirectional"))
    )
    (net (code "32") (name "Net-(IC1-CT)") (class "Default")
      (node (ref "C_DELAY") (pin "1") (pinfunction "1_1") (pintype "passive"))
      (node (ref "IC1") (pin "5") (pinfunction "CT_5") (pintype "bidirectional"))
    )
    (net (code "33") (name "Net-(J2-PadA5)") (class "Default")
      (node (ref "J2") (pin "A5") (pinfunction "A5_A5") (pintype "bidirectional"))
      (node (ref "R2-USB1") (pin "2") (pinfunction "2_2") (pintype "passive"))
    )
    (net (code "34") (name "Net-(J2-PadB5)") (class "Default")
      (node (ref "J2") (pin "B5") (pinfunction "B5_B5") (pintype "bidirectional"))
      (node (ref "R2-USB") (pin "1") (pinfunction "1_1") (pintype "passive"))
    )
    (net (code "35") (name "Net-(MCP73831-PROG)") (class "Default")
      (node (ref "MCP73831") (pin "5") (pinfunction "PROG_5") (pintype "input"))
      (node (ref "R2_BAT") (pin "2") (pinfunction "2_2") (pintype "passive"))
    )
    (net (code "36") (name "Net-(MCP73831-STAT)") (class "Default")
      (node (ref "MCP73831") (pin "1") (pinfunction "STAT_1") (pintype "output"))
      (node (ref "R1_BAT") (pin "1") (pinfunction "1_1") (pintype "passive"))
    )
    (net (code "37") (name "PREVGH") (class "Default")
      (node (ref "D5") (pin "1") (pinfunction "K_1") (pintype "bidirectional"))
      (node (ref "EPD_C9") (pin "2") (pinfunction "2_2") (pintype "passive"))
      (node (ref "J1") (pin "21") (pinfunction "21_21") (pintype "bidirectional"))
    )
    (net (code "38") (name "PREVGL") (class "Default")
      (node (ref "D4") (pin "2") (pinfunction "A_2") (pintype "bidirectional"))
      (node (ref "EPD_C11") (pin "2") (pinfunction "2_2") (pintype "passive"))
      (node (ref "J1") (pin "23") (pinfunction "23_23") (pintype "bidirectional"))
    )
    (net (code "39") (name "RESE") (class "Default")
      (node (ref "J1") (pin "3") (pinfunction "3_3") (pintype "bidirectional"))
      (node (ref "Q3") (pin "2") (pinfunction "S_2") (pintype "bidirectional"))
      (node (ref "R3") (pin "1") (pinfunction "1_1") (pintype "passive"))
    )
    (net (code "40") (name "RESE'") (class "Default")
      (node (ref "R2") (pin "2") (pinfunction "2_2") (pintype "passive"))
      (node (ref "R3") (pin "2") (pinfunction "2_2") (pintype "passive"))
      (node (ref "SJ1") (pin "2") (pinfunction "2_2") (pintype "passive"))
    )
    (net (code "41") (name "RESET") (class "Default")
      (node (ref "C5") (pin "1") (pinfunction "1_1") (pintype "passive"))
      (node (ref "IC1") (pin "1") (pinfunction "VOUT_1") (pintype "bidirectional"))
      (node (ref "RESET_BUTTON") (pin "3") (pinfunction "3_3") (pintype "passive"))
      (node (ref "RESET_BUTTON") (pin "4") (pinfunction "4_4") (pintype "passive"))
      (node (ref "R_RESET") (pin "1") (pinfunction "1_1") (pintype "passive"))
      (node (ref "U2") (pin "3") (pinfunction "EN_3") (pintype "input"))
    )
    (net (code "42") (name "RTC_RST") (class "Default")
      (node (ref "U2") (pin "16") (pinfunction "IO18_16") (pintype "bidirectional"))
      (node (ref "U3") (pin "4") (pinfunction "~{RST}_4") (pintype "input"))
    )
    (net (code "43") (name "RX") (class "Default")
      (node (ref "TP2") (pin "TP") (pinfunction "TP_TP") (pintype "input"))
      (node (ref "U2") (pin "24") (pinfunction "RXD0/GPIO17_24") (pintype "bidirectional"))
    )
    (net (code "44") (name "SCK") (class "Default")
      (node (ref "D10") (pin "1") (pinfunction "1_1") (pintype "passive"))
      (node (ref "J1") (pin "13") (pinfunction "13_13") (pintype "bidirectional"))
      (node (ref "J4") (pin "P5") (pinfunction "CLK_P5") (pintype "bidirectional"))
      (node (ref "R6") (pin "1") (pinfunction "1_1") (pintype "passive"))
      (node (ref "TP8") (pin "TP") (pinfunction "TP_TP") (pintype "input"))
      (node (ref "U1") (pin "6") (pinfunction "CLK_6") (pintype "input"))
      (node (ref "U2") (pin "6") (pinfunction "IO6_6") (pintype "bidirectional"))
    )
    (net (code "45") (name "SCL") (class "Default")
      (node (ref "J3") (pin "4") (pinfunction "4_4") (pintype "passive"))
      (node (ref "R2-PINH") (pin "1") (pinfunction "1_1") (pintype "passive"))
      (node (ref "SENSOR2") (pin "4") (pinfunction "SCK_4") (pintype "input"))
      (node (ref "U2") (pin "20") (pinfunction "IO22_20") (pintype "bidirectional"))
      (node (ref "U3") (pin "16") (pinfunction "SCL_16") (pintype "input"))
      (node (ref "U4") (pin "7") (pinfunction "SCL_7") (pintype "input"))
    )
    (net (code "46") (name "SDA") (class "Default")
      (node (ref "J3") (pin "3") (pinfunction "3_3") (pintype "passive"))
      (node (ref "R1_PINH") (pin "1") (pinfunction "1_1") (pintype "passive"))
      (node (ref "SENSOR2") (pin "3") (pinfunction "SDI_3") (pintype "bidirectional"))
      (node (ref "U2") (pin "19") (pinfunction "IO21_19") (pintype "bidirectional"))
      (node (ref "U3") (pin "15") (pinfunction "SDA_15") (pintype "bidirectional"))
      (node (ref "U4") (pin "8") (pinfunction "SDA_8") (pintype "bidirectional"))
    )
    (net (code "47") (name "SRC") (class "Default")
      (node (ref "C4") (pin "2") (pinfunction "2_2") (pintype "passive"))
      (node (ref "D5") (pin "2") (pinfunction "A_2") (pintype "bidirectional"))
      (node (ref "L1") (pin "1") (pinfunction "1_1") (pintype "passive"))
      (node (ref "Q3") (pin "3") (pinfunction "D_3") (pintype "bidirectional"))
    )
    (net (code "48") (name "SS_SD") (class "Default")
      (node (ref "D8") (pin "1") (pinfunction "1_1") (pintype "passive"))
      (node (ref "J4") (pin "P2") (pinfunction "CD/DAT3_P2") (pintype "bidirectional"))
      (node (ref "R10") (pin "1") (pinfunction "1_1") (pintype "passive"))
      (node (ref "U2") (pin "4") (pinfunction "IO4_4") (pintype "bidirectional"))
    )
    (net (code "49") (name "TX") (class "Default")
      (node (ref "TP1") (pin "TP") (pinfunction "TP_TP") (pintype "input"))
      (node (ref "U2") (pin "25") (pinfunction "TXD0/GPIO16_25") (pintype "bidirectional"))
    )
    (net (code "50") (name "USB_D+") (class "Default")
      (node (ref "D1") (pin "1") (pinfunction "I/O1_1_1") (pintype "bidirectional"))
      (node (ref "U2") (pin "14") (pinfunction "IO13_14") (pintype "bidirectional"))
    )
    (net (code "51") (name "USB_D-") (class "Default")
      (node (ref "D1") (pin "3") (pinfunction "I/O2_1_3") (pintype "bidirectional"))
      (node (ref "U2") (pin "13") (pinfunction "IO12_13") (pintype "bidirectional"))
    )
    (net (code "52") (name "VBAT") (class "Default")
      (node (ref "C2_BAT") (pin "1") (pinfunction "1_1") (pintype "passive"))
      (node (ref "MCP73831") (pin "3") (pinfunction "VBAT_3") (pintype "power_in"))
      (node (ref "Q1") (pin "3") (pinfunction "D_3") (pintype "bidirectional"))
      (node (ref "TP3") (pin "TP") (pinfunction "TP_TP") (pintype "input"))
      (node (ref "U4") (pin "2") (pinfunction "CELL_2") (pintype "power_in"))
      (node (ref "U4") (pin "3") (pinfunction "VDD_3") (pintype "power_in"))
    )
    (net (code "53") (name "VBUS") (class "Default")
      (node (ref "C1_BAT") (pin "1") (pinfunction "1_1") (pintype "passive"))
      (node (ref "C4_USB") (pin "1") (pinfunction "1_1") (pintype "passive"))
      (node (ref "C5_USB") (pin "1") (pinfunction "1_1") (pintype "passive"))
      (node (ref "CHG_LED") (pin "A") (pinfunction "A_A") (pintype "passive"))
      (node (ref "D1") (pin "5") (pinfunction "VBUS_5") (pintype "bidirectional"))
      (node (ref "D2") (pin "2") (pinfunction "ANODE_2") (pintype "bidirectional"))
      (node (ref "MCP73831") (pin "4") (pinfunction "VIN_4") (pintype "power_in"))
      (node (ref "PFMF.050.1") (pin "2") (pinfunction "2_2") (pintype "passive"))
      (node (ref "Q1") (pin "1") (pinfunction "G_1") (pintype "bidirectional"))
      (node (ref "R1_PWRUSB") (pin "2") (pinfunction "2_2") (pintype "passive"))
      (node (ref "TP14") (pin "TP") (pinfunction "TP_TP") (pintype "input"))
    )
    (net (code "54") (name "VRTC") (class "Default")
      (node (ref "C10_SUPERCAP") (pin "2") (pinfunction "2_2") (pintype "passive"))
      (node (ref "C8") (pin "1") (pinfunction "1_1") (pintype "passive"))
      (node (ref "R_CAPACITOR") (pin "2") (pinfunction "2_2") (pintype "passive"))
      (node (ref "U3") (pin "14") (pinfunction "VBAT_14") (pintype "power_in"))
    )
    (net (code "55") (name "VUSB") (class "Default")
      (node (ref "J2") (pin "A4") (pinfunction "A4_A4") (pintype "bidirectional"))
      (node (ref "J2") (pin "A9") (pinfunction "A9_A9") (pintype "bidirectional"))
      (node (ref "J2") (pin "B4") (pinfunction "B4_B4") (pintype "bidirectional"))
      (node (ref "J2") (pin "B9") (pinfunction "B9_B9") (pintype "bidirectional"))
      (node (ref "PFMF.050.1") (pin "1") (pinfunction "1_1") (pintype "passive"))
    )
    (net (code "56") (name "unconnected-(IC1-NC-Pad4)") (class "Default")
      (node (ref "IC1") (pin "4") (pinfunction "NC_4") (pintype "no_connect"))
    )
    (net (code "57") (name "unconnected-(IC4-NC-Pad4)") (class "Default")
      (node (ref "IC4") (pin "4") (pinfunction "NC_4") (pintype "no_connect"))
    )
    (net (code "58") (name "unconnected-(J1-Pad1)") (class "Default")
      (node (ref "J1") (pin "1") (pinfunction "1_1") (pintype "bidirectional"))
    )
    (net (code "59") (name "unconnected-(J1-Pad6)") (class "Default")
      (node (ref "J1") (pin "6") (pinfunction "6_6") (pintype "bidirectional"))
    )
    (net (code "60") (name "unconnected-(J1-Pad7)") (class "Default")
      (node (ref "J1") (pin "7") (pinfunction "7_7") (pintype "bidirectional"))
    )
    (net (code "61") (name "unconnected-(J2-PadA8)") (class "Default")
      (node (ref "J2") (pin "A8") (pinfunction "A8_A8") (pintype "bidirectional"))
    )
    (net (code "62") (name "unconnected-(J2-PadB8)") (class "Default")
      (node (ref "J2") (pin "B8") (pinfunction "B8_B8") (pintype "bidirectional"))
    )
    (net (code "63") (name "unconnected-(J4-DAT1-PadP8)") (class "Default")
      (node (ref "J4") (pin "P8") (pinfunction "DAT1_P8") (pintype "bidirectional"))
    )
    (net (code "64") (name "unconnected-(J4-DAT2-PadP1)") (class "Default")
      (node (ref "J4") (pin "P1") (pinfunction "DAT2_P1") (pintype "bidirectional"))
    )
    (net (code "65") (name "unconnected-(J4-DETECTION_1-PadS1)") (class "Default")
      (node (ref "J4") (pin "S1") (pinfunction "DETECTION_1_S1") (pintype "bidirectional"))
    )
    (net (code "66") (name "unconnected-(J4-DETECTION_2-PadS2)") (class "Default")
      (node (ref "J4") (pin "S2") (pinfunction "DETECTION_2_S2") (pintype "bidirectional"))
    )
    (net (code "67") (name "unconnected-(U2-NC-Pad22)") (class "Default")
      (node (ref "U2") (pin "22") (pinfunction "NC_22") (pintype "no_connect"))
    )
    (net (code "68") (name "unconnected-(U4-~{ALERT}-Pad5)") (class "Default")
      (node (ref "U4") (pin "5") (pinfunction "~{ALERT}_5") (pintype "output"))
    )
  )
)
